# HVPulser0_1.net
KiCad netlist of a schematic drawn in EAGLE
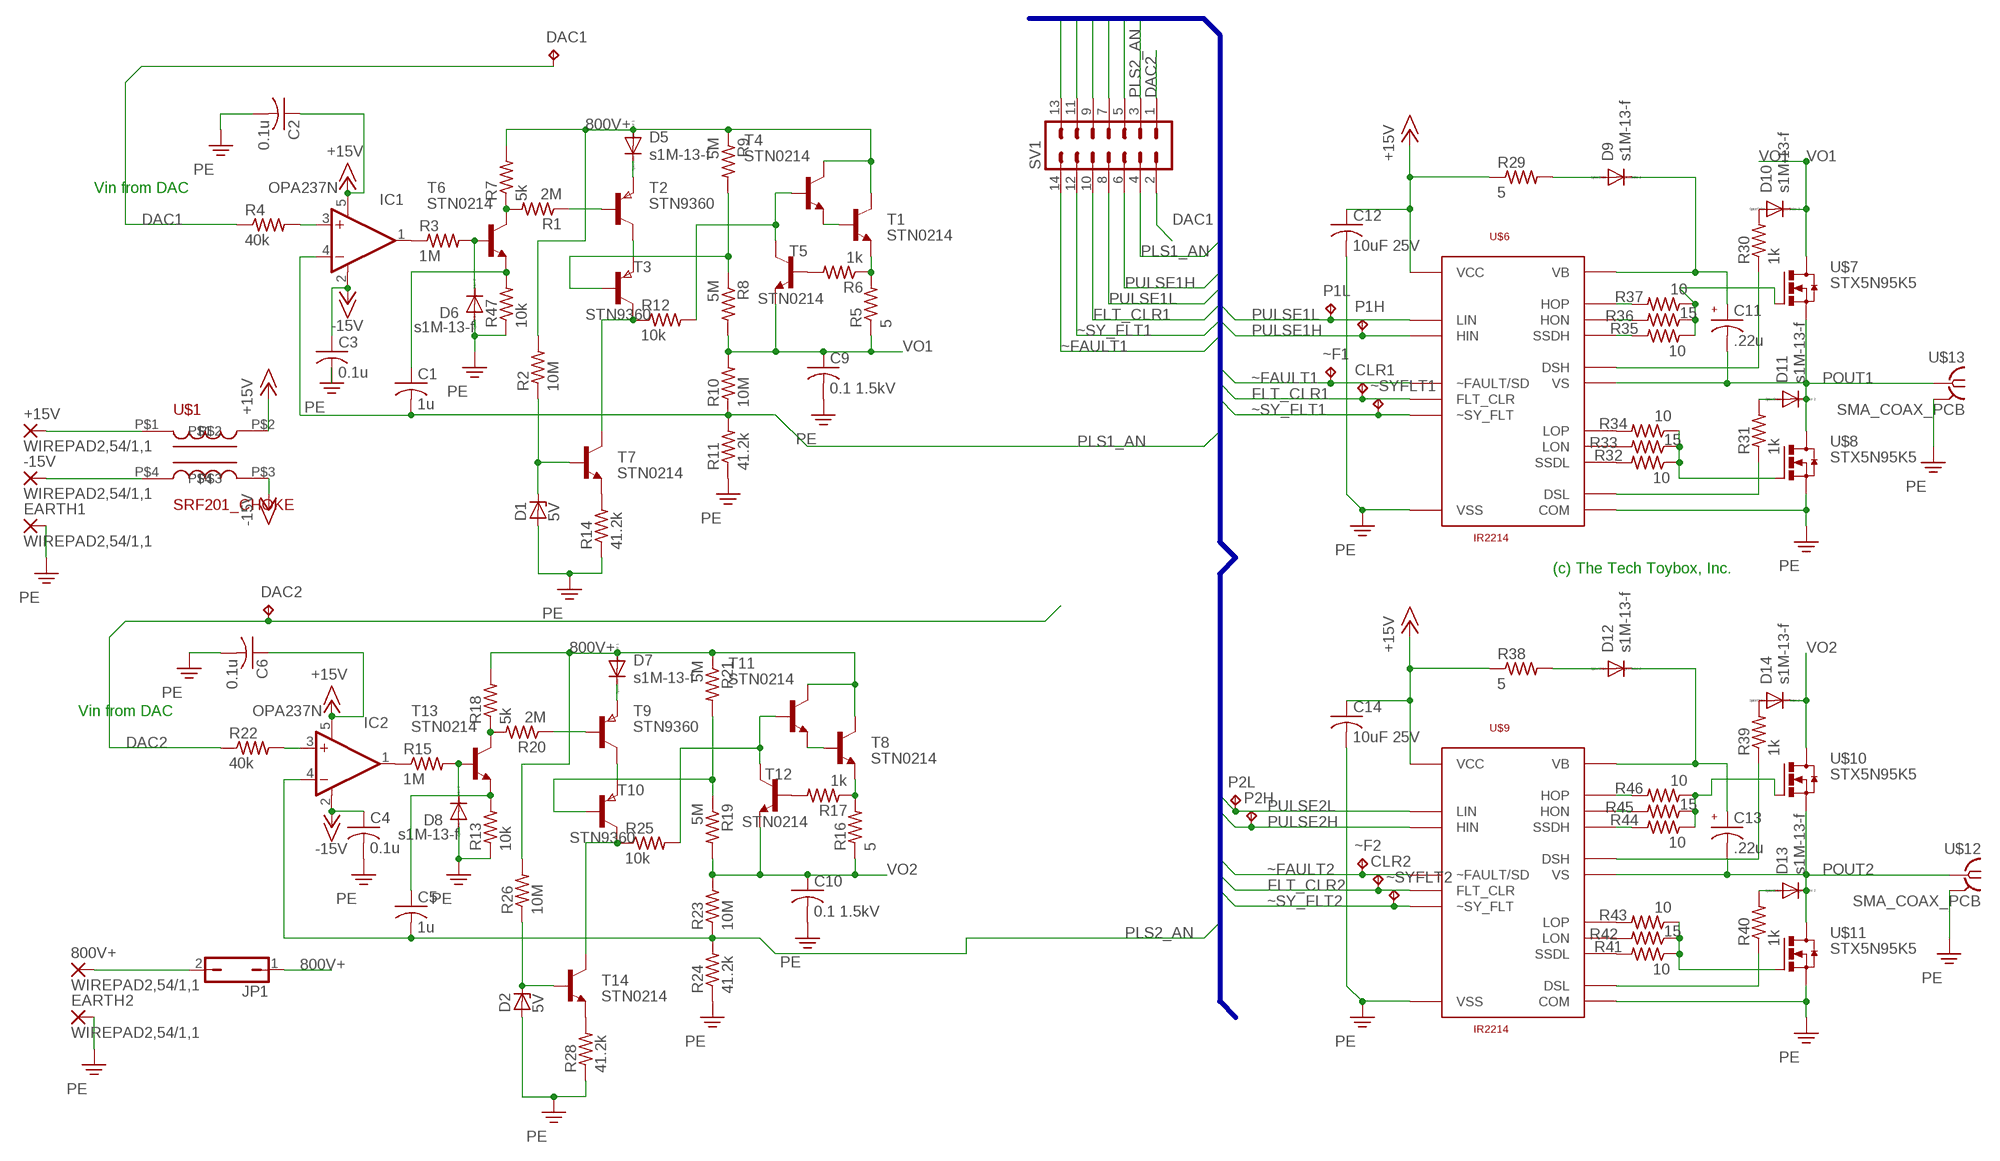
[diagram p0: schematic, sheet 1]

(export (version "E")
  (design (tool "Eeschema 10.0.6"))
  (components
    (comp (ref "+15V")
      (value "WIREPAD2,54/1,1")
      (footprint "eagle-import:2,54_1,1")
      (libsource (lib "eagle-import") (part "WIREPAD2,54/1,1"))
    )
    (comp (ref "-15V")
      (value "WIREPAD2,54/1,1")
      (footprint "eagle-import:2,54_1,1")
      (libsource (lib "eagle-import") (part "WIREPAD2,54/1,1"))
    )
    (comp (ref "800V+")
      (value "WIREPAD2,54/1,1")
      (footprint "eagle-import:2,54_1,1")
      (libsource (lib "eagle-import") (part "WIREPAD2,54/1,1"))
    )
    (comp (ref "C1")
      (value "1u")
      (footprint "eagle-import:C0805")
      (libsource (lib "eagle-import") (part "rcl_C-USC0805"))
    )
    (comp (ref "C2")
      (value "0.1u")
      (footprint "eagle-import:C0805")
      (libsource (lib "eagle-import") (part "rcl_C-USC0805"))
    )
    (comp (ref "C3")
      (value "0.1u")
      (footprint "eagle-import:C0805")
      (libsource (lib "eagle-import") (part "rcl_C-USC0805"))
    )
    (comp (ref "C4")
      (value "0.1u")
      (footprint "eagle-import:C0805")
      (libsource (lib "eagle-import") (part "rcl_C-USC0805"))
    )
    (comp (ref "C5")
      (value "1u")
      (footprint "eagle-import:C0805")
      (libsource (lib "eagle-import") (part "rcl_C-USC0805"))
    )
    (comp (ref "C6")
      (value "0.1u")
      (footprint "eagle-import:C0805")
      (libsource (lib "eagle-import") (part "rcl_C-USC0805"))
    )
    (comp (ref "C9")
      (value "0.1 1.5kV")
      (footprint "eagle-import:C2225K")
      (libsource (lib "eagle-import") (part "rcl_C-USC2225K"))
    )
    (comp (ref "C10")
      (value "0.1 1.5kV")
      (footprint "eagle-import:C2225K")
      (libsource (lib "eagle-import") (part "rcl_C-USC2225K"))
    )
    (comp (ref "C11")
      (value ".22u")
      (footprint "eagle-import:C050-035X075")
      (fields (field (name "PARTNO") "C1608X7R1H224K080AB"))
      (libsource (lib "eagle-import") (part "C-US050-035X075"))
    )
    (comp (ref "C12")
      (value "10uF 25V")
      (footprint "eagle-import:C0805")
      (libsource (lib "eagle-import") (part "rcl_C-USC0805"))
    )
    (comp (ref "C13")
      (value ".22u")
      (footprint "eagle-import:C050-035X075")
      (fields (field (name "PARTNO") "C1608X7R1H224K080AB"))
      (libsource (lib "eagle-import") (part "C-US050-035X075"))
    )
    (comp (ref "C14")
      (value "10uF 25V")
      (footprint "eagle-import:C0805")
      (libsource (lib "eagle-import") (part "rcl_C-USC0805"))
    )
    (comp (ref "CLR1")
      (value "TPTP10R")
      (footprint "eagle-import:TP10R")
      (libsource (lib "eagle-import") (part "TPTP10R"))
    )
    (comp (ref "CLR2")
      (value "TPTP10R")
      (footprint "eagle-import:TP10R")
      (libsource (lib "eagle-import") (part "TPTP10R"))
    )
    (comp (ref "D1")
      (value "5V")
      (footprint "eagle-import:DO41Z10")
      (libsource (lib "eagle-import") (part "ZENER-DIODEDO41Z10"))
    )
    (comp (ref "D2")
      (value "5V")
      (footprint "eagle-import:DO41Z10")
      (libsource (lib "eagle-import") (part "ZENER-DIODEDO41Z10"))
    )
    (comp (ref "D5")
      (value "s1M-13-f")
      (footprint "eagle-import:DO214AC")
      (libsource (lib "eagle-import") (part "DIODE-DO214AC"))
    )
    (comp (ref "D6")
      (value "s1M-13-f")
      (footprint "eagle-import:DO214AC")
      (libsource (lib "eagle-import") (part "DIODE-DO214AC"))
    )
    (comp (ref "D7")
      (value "s1M-13-f")
      (footprint "eagle-import:DO214AC")
      (libsource (lib "eagle-import") (part "DIODE-DO214AC"))
    )
    (comp (ref "D8")
      (value "s1M-13-f")
      (footprint "eagle-import:DO214AC")
      (libsource (lib "eagle-import") (part "DIODE-DO214AC"))
    )
    (comp (ref "D9")
      (value "s1M-13-f")
      (footprint "eagle-import:DO214AC")
      (libsource (lib "eagle-import") (part "DIODE-DO214AC"))
    )
    (comp (ref "D10")
      (value "s1M-13-f")
      (footprint "eagle-import:DO214AC")
      (libsource (lib "eagle-import") (part "DIODE-DO214AC"))
    )
    (comp (ref "D11")
      (value "s1M-13-f")
      (footprint "eagle-import:DO214AC")
      (libsource (lib "eagle-import") (part "DIODE-DO214AC"))
    )
    (comp (ref "D12")
      (value "s1M-13-f")
      (footprint "eagle-import:DO214AC")
      (libsource (lib "eagle-import") (part "DIODE-DO214AC"))
    )
    (comp (ref "D13")
      (value "s1M-13-f")
      (footprint "eagle-import:DO214AC")
      (libsource (lib "eagle-import") (part "DIODE-DO214AC"))
    )
    (comp (ref "D14")
      (value "s1M-13-f")
      (footprint "eagle-import:DO214AC")
      (libsource (lib "eagle-import") (part "DIODE-DO214AC"))
    )
    (comp (ref "DAC1")
      (value "TPTP10R")
      (footprint "eagle-import:TP10R")
      (libsource (lib "eagle-import") (part "TPTP10R"))
    )
    (comp (ref "DAC2")
      (value "TPTP10R")
      (footprint "eagle-import:TP10R")
      (libsource (lib "eagle-import") (part "TPTP10R"))
    )
    (comp (ref "EARTH1")
      (value "WIREPAD2,54/1,1")
      (footprint "eagle-import:2,54_1,1")
      (libsource (lib "eagle-import") (part "WIREPAD2,54/1,1"))
    )
    (comp (ref "EARTH2")
      (value "WIREPAD2,54/1,1")
      (footprint "eagle-import:2,54_1,1")
      (libsource (lib "eagle-import") (part "WIREPAD2,54/1,1"))
    )
    (comp (ref "IC1")
      (value "OPA237N")
      (footprint "eagle-import:SOT23-5")
      (fields (field (name "MF") "TEXAS INSTRUMENTS") (field (name "MPN") "OPA237NA/250"))
      (libsource (lib "eagle-import") (part "OPA237N"))
    )
    (comp (ref "IC2")
      (value "OPA237N")
      (footprint "eagle-import:SOT23-5")
      (fields (field (name "MF") "TEXAS INSTRUMENTS") (field (name "MPN") "OPA237NA/250"))
      (libsource (lib "eagle-import") (part "OPA237N"))
    )
    (comp (ref "JP1")
      (value "JP1Q")
      (footprint "eagle-import:JP1")
      (libsource (lib "eagle-import") (part "JP1Q"))
    )
    (comp (ref "P1H")
      (value "TPTP10R")
      (footprint "eagle-import:TP10R")
      (libsource (lib "eagle-import") (part "TPTP10R"))
    )
    (comp (ref "P1L")
      (value "TPTP10R")
      (footprint "eagle-import:TP10R")
      (libsource (lib "eagle-import") (part "TPTP10R"))
    )
    (comp (ref "P2H")
      (value "TPTP10R")
      (footprint "eagle-import:TP10R")
      (libsource (lib "eagle-import") (part "TPTP10R"))
    )
    (comp (ref "P2L")
      (value "TPTP10R")
      (footprint "eagle-import:TP10R")
      (libsource (lib "eagle-import") (part "TPTP10R"))
    )
    (comp (ref "R1")
      (value "2M")
      (footprint "eagle-import:P0613_15")
      (libsource (lib "eagle-import") (part "R-US_0613/15"))
    )
    (comp (ref "R2")
      (value "10M")
      (footprint "eagle-import:P0613_15")
      (libsource (lib "eagle-import") (part "R-US_0613/15"))
    )
    (comp (ref "R3")
      (value "1M")
      (footprint "eagle-import:R0603")
      (libsource (lib "eagle-import") (part "R-US_R0603"))
    )
    (comp (ref "R4")
      (value "40k")
      (footprint "eagle-import:R0603")
      (libsource (lib "eagle-import") (part "R-US_R0603"))
    )
    (comp (ref "R5")
      (value "5")
      (footprint "eagle-import:P0613_15")
      (libsource (lib "eagle-import") (part "R-US_0613/15"))
    )
    (comp (ref "R6")
      (value "1k")
      (footprint "eagle-import:P0613_15")
      (libsource (lib "eagle-import") (part "R-US_0613/15"))
    )
    (comp (ref "R7")
      (value "5k")
      (footprint "eagle-import:R0603")
      (libsource (lib "eagle-import") (part "R-US_R0603"))
    )
    (comp (ref "R8")
      (value "5M")
      (footprint "eagle-import:P0613_15")
      (libsource (lib "eagle-import") (part "R-US_0613/15"))
    )
    (comp (ref "R9")
      (value "5M")
      (footprint "eagle-import:P0613_15")
      (libsource (lib "eagle-import") (part "R-US_0613/15"))
    )
    (comp (ref "R10")
      (value "10M")
      (footprint "eagle-import:P0613_15")
      (libsource (lib "eagle-import") (part "R-US_0613/15"))
    )
    (comp (ref "R11")
      (value "41.2k")
      (footprint "eagle-import:P0613_15")
      (libsource (lib "eagle-import") (part "R-US_0613/15"))
    )
    (comp (ref "R12")
      (value "10k")
      (footprint "eagle-import:R0603")
      (libsource (lib "eagle-import") (part "R-US_R0603"))
    )
    (comp (ref "R13")
      (value "10k")
      (footprint "eagle-import:R0805")
      (libsource (lib "eagle-import") (part "R-US_R0805"))
    )
    (comp (ref "R14")
      (value "41.2k")
      (footprint "eagle-import:P0613_15")
      (libsource (lib "eagle-import") (part "R-US_0613/15"))
    )
    (comp (ref "R15")
      (value "1M")
      (footprint "eagle-import:R0603")
      (libsource (lib "eagle-import") (part "R-US_R0603"))
    )
    (comp (ref "R16")
      (value "5")
      (footprint "eagle-import:P0613_15")
      (libsource (lib "eagle-import") (part "R-US_0613/15"))
    )
    (comp (ref "R17")
      (value "1k")
      (footprint "eagle-import:P0613_15")
      (libsource (lib "eagle-import") (part "R-US_0613/15"))
    )
    (comp (ref "R18")
      (value "5k")
      (footprint "eagle-import:R0603")
      (libsource (lib "eagle-import") (part "R-US_R0603"))
    )
    (comp (ref "R19")
      (value "5M")
      (footprint "eagle-import:P0613_15")
      (libsource (lib "eagle-import") (part "R-US_0613/15"))
    )
    (comp (ref "R20")
      (value "2M")
      (footprint "eagle-import:P0613_15")
      (libsource (lib "eagle-import") (part "R-US_0613/15"))
    )
    (comp (ref "R21")
      (value "5M")
      (footprint "eagle-import:P0613_15")
      (libsource (lib "eagle-import") (part "R-US_0613/15"))
    )
    (comp (ref "R22")
      (value "40k")
      (footprint "eagle-import:R0603")
      (libsource (lib "eagle-import") (part "R-US_R0603"))
    )
    (comp (ref "R23")
      (value "10M")
      (footprint "eagle-import:P0613_15")
      (libsource (lib "eagle-import") (part "R-US_0613/15"))
    )
    (comp (ref "R24")
      (value "41.2k")
      (footprint "eagle-import:P0613_15")
      (libsource (lib "eagle-import") (part "R-US_0613/15"))
    )
    (comp (ref "R25")
      (value "10k")
      (footprint "eagle-import:R0603")
      (libsource (lib "eagle-import") (part "R-US_R0603"))
    )
    (comp (ref "R26")
      (value "10M")
      (footprint "eagle-import:P0613_15")
      (libsource (lib "eagle-import") (part "R-US_0613/15"))
    )
    (comp (ref "R28")
      (value "41.2k")
      (footprint "eagle-import:P0613_15")
      (libsource (lib "eagle-import") (part "R-US_0613/15"))
    )
    (comp (ref "R29")
      (value "5")
      (footprint "eagle-import:0207_10")
      (libsource (lib "eagle-import") (part "R-US_0207/10"))
    )
    (comp (ref "R30")
      (value "1k")
      (footprint "eagle-import:R0603")
      (libsource (lib "eagle-import") (part "R-US_R0603"))
    )
    (comp (ref "R31")
      (value "1k")
      (footprint "eagle-import:R0603")
      (libsource (lib "eagle-import") (part "R-US_R0603"))
    )
    (comp (ref "R32")
      (value "10")
      (footprint "eagle-import:R0805")
      (libsource (lib "eagle-import") (part "R-US_R0805"))
    )
    (comp (ref "R33")
      (value "15")
      (footprint "eagle-import:R0805")
      (libsource (lib "eagle-import") (part "R-US_R0805"))
    )
    (comp (ref "R34")
      (value "10")
      (footprint "eagle-import:R0805")
      (libsource (lib "eagle-import") (part "R-US_R0805"))
    )
    (comp (ref "R35")
      (value "10")
      (footprint "eagle-import:R0805")
      (libsource (lib "eagle-import") (part "R-US_R0805"))
    )
    (comp (ref "R36")
      (value "15")
      (footprint "eagle-import:R0805")
      (libsource (lib "eagle-import") (part "R-US_R0805"))
    )
    (comp (ref "R37")
      (value "10")
      (footprint "eagle-import:R0805")
      (libsource (lib "eagle-import") (part "R-US_R0805"))
    )
    (comp (ref "R38")
      (value "5")
      (footprint "eagle-import:0207_10")
      (libsource (lib "eagle-import") (part "R-US_0207/10"))
    )
    (comp (ref "R39")
      (value "1k")
      (footprint "eagle-import:R0603")
      (libsource (lib "eagle-import") (part "R-US_R0603"))
    )
    (comp (ref "R40")
      (value "1k")
      (footprint "eagle-import:R0603")
      (libsource (lib "eagle-import") (part "R-US_R0603"))
    )
    (comp (ref "R41")
      (value "10")
      (footprint "eagle-import:R0805")
      (libsource (lib "eagle-import") (part "R-US_R0805"))
    )
    (comp (ref "R42")
      (value "15")
      (footprint "eagle-import:R0805")
      (libsource (lib "eagle-import") (part "R-US_R0805"))
    )
    (comp (ref "R43")
      (value "10")
      (footprint "eagle-import:R0805")
      (libsource (lib "eagle-import") (part "R-US_R0805"))
    )
    (comp (ref "R44")
      (value "10")
      (footprint "eagle-import:R0805")
      (libsource (lib "eagle-import") (part "R-US_R0805"))
    )
    (comp (ref "R45")
      (value "15")
      (footprint "eagle-import:R0805")
      (libsource (lib "eagle-import") (part "R-US_R0805"))
    )
    (comp (ref "R46")
      (value "10")
      (footprint "eagle-import:R0805")
      (libsource (lib "eagle-import") (part "R-US_R0805"))
    )
    (comp (ref "R47")
      (value "10k")
      (footprint "eagle-import:R0805")
      (libsource (lib "eagle-import") (part "R-US_R0805"))
    )
    (comp (ref "SV1")
      (value "MA07-2")
      (footprint "eagle-import:MA07-2")
      (libsource (lib "eagle-import") (part "MA07-2"))
    )
    (comp (ref "T1")
      (value "STN0214")
      (footprint "eagle-import:SOT223")
      (libsource (lib "eagle-import") (part "-NPN-SOT223"))
    )
    (comp (ref "T2")
      (value "STN9360")
      (footprint "eagle-import:SOT223")
      (fields (field (name "MPN") "DJT4030P-13"))
      (libsource (lib "eagle-import") (part "PNPSOT223"))
    )
    (comp (ref "T3")
      (value "STN9360")
      (footprint "eagle-import:SOT223")
      (fields (field (name "MPN") "DJT4030P-13"))
      (libsource (lib "eagle-import") (part "PNPSOT223"))
    )
    (comp (ref "T4")
      (value "STN0214")
      (footprint "eagle-import:SOT223")
      (libsource (lib "eagle-import") (part "-NPN-SOT223"))
    )
    (comp (ref "T5")
      (value "STN0214")
      (footprint "eagle-import:SOT223")
      (libsource (lib "eagle-import") (part "-NPN-SOT223"))
    )
    (comp (ref "T6")
      (value "STN0214")
      (footprint "eagle-import:SOT223")
      (libsource (lib "eagle-import") (part "-NPN-SOT223"))
    )
    (comp (ref "T7")
      (value "STN0214")
      (footprint "eagle-import:SOT223")
      (libsource (lib "eagle-import") (part "-NPN-SOT223"))
    )
    (comp (ref "T8")
      (value "STN0214")
      (footprint "eagle-import:SOT223")
      (libsource (lib "eagle-import") (part "-NPN-SOT223"))
    )
    (comp (ref "T9")
      (value "STN9360")
      (footprint "eagle-import:SOT223")
      (fields (field (name "MPN") "DJT4030P-13"))
      (libsource (lib "eagle-import") (part "PNPSOT223"))
    )
    (comp (ref "T10")
      (value "STN9360")
      (footprint "eagle-import:SOT223")
      (fields (field (name "MPN") "DJT4030P-13"))
      (libsource (lib "eagle-import") (part "PNPSOT223"))
    )
    (comp (ref "T11")
      (value "STN0214")
      (footprint "eagle-import:SOT223")
      (libsource (lib "eagle-import") (part "-NPN-SOT223"))
    )
    (comp (ref "T12")
      (value "STN0214")
      (footprint "eagle-import:SOT223")
      (libsource (lib "eagle-import") (part "-NPN-SOT223"))
    )
    (comp (ref "T13")
      (value "STN0214")
      (footprint "eagle-import:SOT223")
      (libsource (lib "eagle-import") (part "-NPN-SOT223"))
    )
    (comp (ref "T14")
      (value "STN0214")
      (footprint "eagle-import:SOT223")
      (libsource (lib "eagle-import") (part "-NPN-SOT223"))
    )
    (comp (ref "U$1")
      (value "SRF201_CHOKE")
      (footprint "eagle-import:CHOKE_BOURNES_SRF2012")
      (libsource (lib "eagle-import") (part "SRF201_CHOKE"))
    )
    (comp (ref "U$6")
      (value "IR2214")
      (footprint "eagle-import:SSOP24-IR-0.65")
      (libsource (lib "eagle-import") (part "IR2214"))
    )
    (comp (ref "U$7")
      (value "STX5N95K5")
      (footprint "eagle-import:TO220AV")
      (libsource (lib "eagle-import") (part "STX5N95K5"))
    )
    (comp (ref "U$8")
      (value "STX5N95K5")
      (footprint "eagle-import:TO220AV")
      (libsource (lib "eagle-import") (part "STX5N95K5"))
    )
    (comp (ref "U$9")
      (value "IR2214")
      (footprint "eagle-import:SSOP24-IR-0.65")
      (libsource (lib "eagle-import") (part "IR2214"))
    )
    (comp (ref "U$10")
      (value "STX5N95K5")
      (footprint "eagle-import:TO220AV")
      (libsource (lib "eagle-import") (part "STX5N95K5"))
    )
    (comp (ref "U$11")
      (value "STX5N95K5")
      (footprint "eagle-import:TO220AV")
      (libsource (lib "eagle-import") (part "STX5N95K5"))
    )
    (comp (ref "U$12")
      (value "SMA_COAX_PCB")
      (footprint "eagle-import:SMA-COAX-V-TECONNECT")
      (libsource (lib "eagle-import") (part "SMA_COAX_PCB"))
    )
    (comp (ref "U$13")
      (value "SMA_COAX_PCB")
      (footprint "eagle-import:SMA-COAX-V-TECONNECT")
      (libsource (lib "eagle-import") (part "SMA_COAX_PCB"))
    )
    (comp (ref "~F1")
      (value "TPTP10R")
      (footprint "eagle-import:TP10R")
      (libsource (lib "eagle-import") (part "TPTP10R"))
    )
    (comp (ref "~F2")
      (value "TPTP10R")
      (footprint "eagle-import:TP10R")
      (libsource (lib "eagle-import") (part "TPTP10R"))
    )
    (comp (ref "~SYFLT1")
      (value "TPTP10R")
      (footprint "eagle-import:TP10R")
      (libsource (lib "eagle-import") (part "TPTP10R"))
    )
    (comp (ref "~SYFLT2")
      (value "TPTP10R")
      (footprint "eagle-import:TP10R")
      (libsource (lib "eagle-import") (part "TPTP10R"))
    )
  )
  (nets
    (net (code "1") (name "+15V") (class "Default")
      (node (ref "C12") (pin "1") (pinfunction "1_1") (pintype "passive"))
      (node (ref "C14") (pin "1") (pinfunction "1_1") (pintype "passive"))
      (node (ref "C2") (pin "1") (pinfunction "1_1") (pintype "passive"))
      (node (ref "C6") (pin "1") (pinfunction "1_1") (pintype "passive"))
      (node (ref "IC1") (pin "5") (pinfunction "V+_5") (pintype "power_in"))
      (node (ref "IC2") (pin "5") (pinfunction "V+_5") (pintype "power_in"))
      (node (ref "R29") (pin "1") (pinfunction "1_1") (pintype "passive"))
      (node (ref "R38") (pin "1") (pinfunction "1_1") (pintype "passive"))
      (node (ref "U$1") (pin "P$2") (pinfunction "P$2_P$2") (pintype "bidirectional"))
      (node (ref "U$6") (pin "P$11") (pinfunction "VCC_P$11") (pintype "bidirectional"))
      (node (ref "U$9") (pin "P$11") (pinfunction "VCC_P$11") (pintype "bidirectional"))
    )
    (net (code "2") (name "-15V") (class "Default")
      (node (ref "C3") (pin "1") (pinfunction "1_1") (pintype "passive"))
      (node (ref "C4") (pin "1") (pinfunction "1_1") (pintype "passive"))
      (node (ref "IC1") (pin "2") (pinfunction "V-_2") (pintype "power_in"))
      (node (ref "IC2") (pin "2") (pinfunction "V-_2") (pintype "power_in"))
      (node (ref "U$1") (pin "P$3") (pinfunction "P$3_P$3") (pintype "bidirectional"))
    )
    (net (code "3") (name "/800V+") (class "Default")
      (node (ref "D5") (pin "A") (pinfunction "A_A") (pintype "passive"))
      (node (ref "D7") (pin "A") (pinfunction "A_A") (pintype "passive"))
      (node (ref "JP1") (pin "1") (pinfunction "1_1") (pintype "passive"))
      (node (ref "R18") (pin "2") (pinfunction "2_2") (pintype "passive"))
      (node (ref "R2") (pin "2") (pinfunction "2_2") (pintype "passive"))
      (node (ref "R21") (pin "1") (pinfunction "1_1") (pintype "passive"))
      (node (ref "R26") (pin "2") (pinfunction "2_2") (pintype "passive"))
      (node (ref "R7") (pin "2") (pinfunction "2_2") (pintype "passive"))
      (node (ref "R9") (pin "1") (pinfunction "1_1") (pintype "passive"))
      (node (ref "T1") (pin "4") (pinfunction "C_4") (pintype "passive"))
      (node (ref "T11") (pin "4") (pinfunction "C_4") (pintype "passive"))
      (node (ref "T4") (pin "4") (pinfunction "C_4") (pintype "passive"))
      (node (ref "T8") (pin "4") (pinfunction "C_4") (pintype "passive"))
    )
    (net (code "4") (name "/DAC1") (class "Default")
      (node (ref "DAC1") (pin "TP") (pinfunction "TP_TP") (pintype "input"))
      (node (ref "R4") (pin "1") (pinfunction "1_1") (pintype "passive"))
      (node (ref "SV1") (pin "2") (pinfunction "2_2") (pintype "passive"))
    )
    (net (code "5") (name "/DAC2") (class "Default")
      (node (ref "DAC2") (pin "TP") (pinfunction "TP_TP") (pintype "input"))
      (node (ref "R22") (pin "1") (pinfunction "1_1") (pintype "passive"))
      (node (ref "SV1") (pin "1") (pinfunction "1_1") (pintype "passive"))
    )
    (net (code "6") (name "/FLT_CLR1") (class "Default")
      (node (ref "CLR1") (pin "TP") (pinfunction "TP_TP") (pintype "input"))
      (node (ref "SV1") (pin "10") (pinfunction "10_10") (pintype "passive"))
      (node (ref "U$6") (pin "P$3") (pinfunction "FLT_CLR_P$3") (pintype "bidirectional"))
    )
    (net (code "7") (name "/FLT_CLR2") (class "Default")
      (node (ref "CLR2") (pin "TP") (pinfunction "TP_TP") (pintype "input"))
      (node (ref "SV1") (pin "9") (pinfunction "9_9") (pintype "passive"))
      (node (ref "U$9") (pin "P$3") (pinfunction "FLT_CLR_P$3") (pintype "bidirectional"))
    )
    (net (code "8") (name "/PLS1_AN") (class "Default")
      (node (ref "C1") (pin "2") (pinfunction "2_2") (pintype "passive"))
      (node (ref "IC1") (pin "4") (pinfunction "-IN_4") (pintype "input"))
      (node (ref "R10") (pin "1") (pinfunction "1_1") (pintype "passive"))
      (node (ref "R11") (pin "2") (pinfunction "2_2") (pintype "passive"))
      (node (ref "SV1") (pin "4") (pinfunction "4_4") (pintype "passive"))
    )
    (net (code "9") (name "/PLS2_AN") (class "Default")
      (node (ref "C5") (pin "2") (pinfunction "2_2") (pintype "passive"))
      (node (ref "IC2") (pin "4") (pinfunction "-IN_4") (pintype "input"))
      (node (ref "R23") (pin "1") (pinfunction "1_1") (pintype "passive"))
      (node (ref "R24") (pin "2") (pinfunction "2_2") (pintype "passive"))
      (node (ref "SV1") (pin "3") (pinfunction "3_3") (pintype "passive"))
    )
    (net (code "10") (name "/POUT1") (class "Default")
      (node (ref "C11") (pin "2") (pinfunction "2_2") (pintype "passive"))
      (node (ref "D11") (pin "C") (pinfunction "C_C") (pintype "passive"))
      (node (ref "U$13") (pin "1") (pinfunction "1_1") (pintype "passive"))
      (node (ref "U$6") (pin "P$19") (pinfunction "VS_P$19") (pintype "bidirectional"))
      (node (ref "U$7") (pin "3") (pinfunction "S_3") (pintype "passive"))
      (node (ref "U$8") (pin "2") (pinfunction "D_2") (pintype "passive"))
    )
    (net (code "11") (name "/POUT2") (class "Default")
      (node (ref "C13") (pin "2") (pinfunction "2_2") (pintype "passive"))
      (node (ref "D13") (pin "C") (pinfunction "C_C") (pintype "passive"))
      (node (ref "U$10") (pin "3") (pinfunction "S_3") (pintype "passive"))
      (node (ref "U$11") (pin "2") (pinfunction "D_2") (pintype "passive"))
      (node (ref "U$12") (pin "1") (pinfunction "1_1") (pintype "passive"))
      (node (ref "U$9") (pin "P$19") (pinfunction "VS_P$19") (pintype "bidirectional"))
    )
    (net (code "12") (name "/PULSE1H") (class "Default")
      (node (ref "P1H") (pin "TP") (pinfunction "TP_TP") (pintype "input"))
      (node (ref "SV1") (pin "6") (pinfunction "6_6") (pintype "passive"))
      (node (ref "U$6") (pin "P$1") (pinfunction "HIN_P$1") (pintype "input"))
    )
    (net (code "13") (name "/PULSE1L") (class "Default")
      (node (ref "P1L") (pin "TP") (pinfunction "TP_TP") (pintype "input"))
      (node (ref "SV1") (pin "8") (pinfunction "8_8") (pintype "passive"))
      (node (ref "U$6") (pin "P$2") (pinfunction "LIN_P$2") (pintype "input"))
    )
    (net (code "14") (name "/PULSE2H") (class "Default")
      (node (ref "P2H") (pin "TP") (pinfunction "TP_TP") (pintype "input"))
      (node (ref "SV1") (pin "13") (pinfunction "13_13") (pintype "passive"))
      (node (ref "U$9") (pin "P$1") (pinfunction "HIN_P$1") (pintype "input"))
    )
    (net (code "15") (name "/PULSE2L") (class "Default")
      (node (ref "P2L") (pin "TP") (pinfunction "TP_TP") (pintype "input"))
      (node (ref "SV1") (pin "11") (pinfunction "11_11") (pintype "passive"))
      (node (ref "U$9") (pin "P$2") (pinfunction "LIN_P$2") (pintype "input"))
    )
    (net (code "16") (name "/VO1") (class "Default")
      (node (ref "C9") (pin "1") (pinfunction "1_1") (pintype "passive"))
      (node (ref "D10") (pin "C") (pinfunction "C_C") (pintype "passive"))
      (node (ref "R10") (pin "2") (pinfunction "2_2") (pintype "passive"))
      (node (ref "R5") (pin "1") (pinfunction "1_1") (pintype "passive"))
      (node (ref "R8") (pin "2") (pinfunction "2_2") (pintype "passive"))
      (node (ref "T5") (pin "3") (pinfunction "E_3") (pintype "passive"))
      (node (ref "U$7") (pin "2") (pinfunction "D_2") (pintype "passive"))
    )
    (net (code "17") (name "/VO2") (class "Default")
      (node (ref "C10") (pin "1") (pinfunction "1_1") (pintype "passive"))
      (node (ref "D14") (pin "C") (pinfunction "C_C") (pintype "passive"))
      (node (ref "R16") (pin "1") (pinfunction "1_1") (pintype "passive"))
      (node (ref "R19") (pin "2") (pinfunction "2_2") (pintype "passive"))
      (node (ref "R23") (pin "2") (pinfunction "2_2") (pintype "passive"))
      (node (ref "T12") (pin "3") (pinfunction "E_3") (pintype "passive"))
      (node (ref "U$10") (pin "2") (pinfunction "D_2") (pintype "passive"))
    )
    (net (code "18") (name "/~{FAULT1}") (class "Default")
      (node (ref "SV1") (pin "14") (pinfunction "14_14") (pintype "passive"))
      (node (ref "U$6") (pin "P$5") (pinfunction "~{FAULT/SD}_P$5") (pintype "bidirectional"))
      (node (ref "~F1") (pin "TP") (pinfunction "TP_TP") (pintype "input"))
    )
    (net (code "19") (name "/~{FAULT2}") (class "Default")
      (node (ref "SV1") (pin "5") (pinfunction "5_5") (pintype "passive"))
      (node (ref "U$9") (pin "P$5") (pinfunction "~{FAULT/SD}_P$5") (pintype "bidirectional"))
      (node (ref "~F2") (pin "TP") (pinfunction "TP_TP") (pintype "input"))
    )
    (net (code "20") (name "/~{SY_FLT1}") (class "Default")
      (node (ref "SV1") (pin "12") (pinfunction "12_12") (pintype "passive"))
      (node (ref "U$6") (pin "P$4") (pinfunction "~{SY_FLT}_P$4") (pintype "bidirectional"))
      (node (ref "~SYFLT1") (pin "TP") (pinfunction "TP_TP") (pintype "input"))
    )
    (net (code "21") (name "/~{SY_FLT2}") (class "Default")
      (node (ref "SV1") (pin "7") (pinfunction "7_7") (pintype "passive"))
      (node (ref "U$9") (pin "P$4") (pinfunction "~{SY_FLT}_P$4") (pintype "bidirectional"))
      (node (ref "~SYFLT2") (pin "TP") (pinfunction "TP_TP") (pintype "input"))
    )
    (net (code "22") (name "Net-(+15V-P)") (class "Default")
      (node (ref "+15V") (pin "1") (pinfunction "P_1") (pintype "passive"))
      (node (ref "U$1") (pin "P$1") (pinfunction "P$1_P$1") (pintype "bidirectional"))
    )
    (net (code "23") (name "Net-(-15V-P)") (class "Default")
      (node (ref "-15V") (pin "1") (pinfunction "P_1") (pintype "passive"))
      (node (ref "U$1") (pin "P$4") (pinfunction "P$4_P$4") (pintype "bidirectional"))
    )
    (net (code "24") (name "Net-(800V+-P)") (class "Default")
      (node (ref "800V+") (pin "1") (pinfunction "P_1") (pintype "passive"))
      (node (ref "JP1") (pin "2") (pinfunction "2_2") (pintype "passive"))
    )
    (net (code "25") (name "Net-(D9-PadA)") (class "Default")
      (node (ref "D9") (pin "A") (pinfunction "A_A") (pintype "passive"))
      (node (ref "R29") (pin "2") (pinfunction "2_2") (pintype "passive"))
    )
    (net (code "26") (name "Net-(D10-PadA)") (class "Default")
      (node (ref "D10") (pin "A") (pinfunction "A_A") (pintype "passive"))
      (node (ref "R30") (pin "2") (pinfunction "2_2") (pintype "passive"))
    )
    (net (code "27") (name "Net-(D11-PadA)") (class "Default")
      (node (ref "D11") (pin "A") (pinfunction "A_A") (pintype "passive"))
      (node (ref "R31") (pin "2") (pinfunction "2_2") (pintype "passive"))
    )
    (net (code "28") (name "Net-(D12-PadA)") (class "Default")
      (node (ref "D12") (pin "A") (pinfunction "A_A") (pintype "passive"))
      (node (ref "R38") (pin "2") (pinfunction "2_2") (pintype "passive"))
    )
    (net (code "29") (name "Net-(D13-PadA)") (class "Default")
      (node (ref "D13") (pin "A") (pinfunction "A_A") (pintype "passive"))
      (node (ref "R40") (pin "2") (pinfunction "2_2") (pintype "passive"))
    )
    (net (code "30") (name "Net-(D14-PadA)") (class "Default")
      (node (ref "D14") (pin "A") (pinfunction "A_A") (pintype "passive"))
      (node (ref "R39") (pin "2") (pinfunction "2_2") (pintype "passive"))
    )
    (net (code "31") (name "Net-(IC1-+IN)") (class "Default")
      (node (ref "IC1") (pin "3") (pinfunction "+IN_3") (pintype "input"))
      (node (ref "R4") (pin "2") (pinfunction "2_2") (pintype "passive"))
    )
    (net (code "32") (name "Net-(IC1-OUT)") (class "Default")
      (node (ref "IC1") (pin "1") (pinfunction "OUT_1") (pintype "output"))
      (node (ref "R3") (pin "1") (pinfunction "1_1") (pintype "passive"))
    )
    (net (code "33") (name "Net-(IC2-+IN)") (class "Default")
      (node (ref "IC2") (pin "3") (pinfunction "+IN_3") (pintype "input"))
      (node (ref "R22") (pin "2") (pinfunction "2_2") (pintype "passive"))
    )
    (net (code "34") (name "Net-(IC2-OUT)") (class "Default")
      (node (ref "IC2") (pin "1") (pinfunction "OUT_1") (pintype "output"))
      (node (ref "R15") (pin "1") (pinfunction "1_1") (pintype "passive"))
    )
    (net (code "35") (name "Net-(T1-B)") (class "Default")
      (node (ref "T1") (pin "1") (pinfunction "B_1") (pintype "passive"))
      (node (ref "T4") (pin "3") (pinfunction "E_3") (pintype "passive"))
    )
    (net (code "36") (name "Net-(T1-E)") (class "Default")
      (node (ref "R5") (pin "2") (pinfunction "2_2") (pintype "passive"))
      (node (ref "R6") (pin "1") (pinfunction "1_1") (pintype "passive"))
      (node (ref "T1") (pin "3") (pinfunction "E_3") (pintype "passive"))
    )
    (net (code "37") (name "Net-(T2-B)") (class "Default")
      (node (ref "R1") (pin "1") (pinfunction "1_1") (pintype "passive"))
      (node (ref "T2") (pin "1") (pinfunction "B_1") (pintype "passive"))
    )
    (net (code "38") (name "Net-(T2-E)") (class "Default")
      (node (ref "D5") (pin "C") (pinfunction "C_C") (pintype "passive"))
      (node (ref "T2") (pin "3") (pinfunction "E_3") (pintype "passive"))
    )
    (net (code "39") (name "Net-(T3-B)") (class "Default")
      (node (ref "R8") (pin "1") (pinfunction "1_1") (pintype "passive"))
      (node (ref "R9") (pin "2") (pinfunction "2_2") (pintype "passive"))
      (node (ref "T3") (pin "1") (pinfunction "B_1") (pintype "passive"))
    )
    (net (code "40") (name "Net-(T3-E)") (class "Default")
      (node (ref "T2") (pin "2") (pinfunction "C_2") (pintype "passive"))
      (node (ref "T2") (pin "4") (pinfunction "C_4") (pintype "passive"))
      (node (ref "T3") (pin "3") (pinfunction "E_3") (pintype "passive"))
    )
    (net (code "41") (name "Net-(T4-B)") (class "Default")
      (node (ref "R12") (pin "2") (pinfunction "2_2") (pintype "passive"))
      (node (ref "T4") (pin "1") (pinfunction "B_1") (pintype "passive"))
      (node (ref "T5") (pin "4") (pinfunction "C_4") (pintype "passive"))
    )
    (net (code "42") (name "Net-(T5-B)") (class "Default")
      (node (ref "R6") (pin "2") (pinfunction "2_2") (pintype "passive"))
      (node (ref "T5") (pin "1") (pinfunction "B_1") (pintype "passive"))
    )
    (net (code "43") (name "Net-(T6-B)") (class "Default")
      (node (ref "D6") (pin "C") (pinfunction "C_C") (pintype "passive"))
      (node (ref "R3") (pin "2") (pinfunction "2_2") (pintype "passive"))
      (node (ref "T6") (pin "1") (pinfunction "B_1") (pintype "passive"))
    )
    (net (code "44") (name "Net-(T6-C)") (class "Default")
      (node (ref "R1") (pin "2") (pinfunction "2_2") (pintype "passive"))
      (node (ref "R7") (pin "1") (pinfunction "1_1") (pintype "passive"))
      (node (ref "T6") (pin "4") (pinfunction "C_4") (pintype "passive"))
    )
    (net (code "45") (name "Net-(T6-E)") (class "Default")
      (node (ref "C1") (pin "1") (pinfunction "1_1") (pintype "passive"))
      (node (ref "R47") (pin "2") (pinfunction "2_2") (pintype "passive"))
      (node (ref "T6") (pin "3") (pinfunction "E_3") (pintype "passive"))
    )
    (net (code "46") (name "Net-(T7-B)") (class "Default")
      (node (ref "D1") (pin "C") (pinfunction "C_C") (pintype "passive"))
      (node (ref "R2") (pin "1") (pinfunction "1_1") (pintype "passive"))
      (node (ref "T7") (pin "1") (pinfunction "B_1") (pintype "passive"))
    )
    (net (code "47") (name "Net-(T7-C)") (class "Default")
      (node (ref "R12") (pin "1") (pinfunction "1_1") (pintype "passive"))
      (node (ref "T3") (pin "2") (pinfunction "C_2") (pintype "passive"))
      (node (ref "T3") (pin "4") (pinfunction "C_4") (pintype "passive"))
      (node (ref "T7") (pin "4") (pinfunction "C_4") (pintype "passive"))
    )
    (net (code "48") (name "Net-(T7-E)") (class "Default")
      (node (ref "R14") (pin "2") (pinfunction "2_2") (pintype "passive"))
      (node (ref "T7") (pin "3") (pinfunction "E_3") (pintype "passive"))
    )
    (net (code "49") (name "Net-(T8-E)") (class "Default")
      (node (ref "R16") (pin "2") (pinfunction "2_2") (pintype "passive"))
      (node (ref "R17") (pin "1") (pinfunction "1_1") (pintype "passive"))
      (node (ref "T8") (pin "3") (pinfunction "E_3") (pintype "passive"))
    )
    (net (code "50") (name "Net-(T9-B)") (class "Default")
      (node (ref "R20") (pin "1") (pinfunction "1_1") (pintype "passive"))
      (node (ref "T9") (pin "1") (pinfunction "B_1") (pintype "passive"))
    )
    (net (code "51") (name "Net-(T9-E)") (class "Default")
      (node (ref "D7") (pin "C") (pinfunction "C_C") (pintype "passive"))
      (node (ref "T9") (pin "3") (pinfunction "E_3") (pintype "passive"))
    )
    (net (code "52") (name "Net-(T10-B)") (class "Default")
      (node (ref "R19") (pin "1") (pinfunction "1_1") (pintype "passive"))
      (node (ref "R21") (pin "2") (pinfunction "2_2") (pintype "passive"))
      (node (ref "T10") (pin "1") (pinfunction "B_1") (pintype "passive"))
    )
    (net (code "53") (name "Net-(T10-E)") (class "Default")
      (node (ref "T10") (pin "3") (pinfunction "E_3") (pintype "passive"))
      (node (ref "T9") (pin "2") (pinfunction "C_2") (pintype "passive"))
      (node (ref "T9") (pin "4") (pinfunction "C_4") (pintype "passive"))
    )
    (net (code "54") (name "Net-(T11-B)") (class "Default")
      (node (ref "R25") (pin "2") (pinfunction "2_2") (pintype "passive"))
      (node (ref "T11") (pin "1") (pinfunction "B_1") (pintype "passive"))
      (node (ref "T12") (pin "4") (pinfunction "C_4") (pintype "passive"))
    )
    (net (code "55") (name "Net-(T11-E)") (class "Default")
      (node (ref "T11") (pin "3") (pinfunction "E_3") (pintype "passive"))
      (node (ref "T8") (pin "1") (pinfunction "B_1") (pintype "passive"))
    )
    (net (code "56") (name "Net-(T12-B)") (class "Default")
      (node (ref "R17") (pin "2") (pinfunction "2_2") (pintype "passive"))
      (node (ref "T12") (pin "1") (pinfunction "B_1") (pintype "passive"))
    )
    (net (code "57") (name "Net-(T13-B)") (class "Default")
      (node (ref "D8") (pin "C") (pinfunction "C_C") (pintype "passive"))
      (node (ref "R15") (pin "2") (pinfunction "2_2") (pintype "passive"))
      (node (ref "T13") (pin "1") (pinfunction "B_1") (pintype "passive"))
    )
    (net (code "58") (name "Net-(T13-C)") (class "Default")
      (node (ref "R18") (pin "1") (pinfunction "1_1") (pintype "passive"))
      (node (ref "R20") (pin "2") (pinfunction "2_2") (pintype "passive"))
      (node (ref "T13") (pin "4") (pinfunction "C_4") (pintype "passive"))
    )
    (net (code "59") (name "Net-(T13-E)") (class "Default")
      (node (ref "C5") (pin "1") (pinfunction "1_1") (pintype "passive"))
      (node (ref "R13") (pin "2") (pinfunction "2_2") (pintype "passive"))
      (node (ref "T13") (pin "3") (pinfunction "E_3") (pintype "passive"))
    )
    (net (code "60") (name "Net-(T14-B)") (class "Default")
      (node (ref "D2") (pin "C") (pinfunction "C_C") (pintype "passive"))
      (node (ref "R26") (pin "1") (pinfunction "1_1") (pintype "passive"))
      (node (ref "T14") (pin "1") (pinfunction "B_1") (pintype "passive"))
    )
    (net (code "61") (name "Net-(T14-C)") (class "Default")
      (node (ref "R25") (pin "1") (pinfunction "1_1") (pintype "passive"))
      (node (ref "T10") (pin "2") (pinfunction "C_2") (pintype "passive"))
      (node (ref "T10") (pin "4") (pinfunction "C_4") (pintype "passive"))
      (node (ref "T14") (pin "4") (pinfunction "C_4") (pintype "passive"))
    )
    (net (code "62") (name "Net-(T14-E)") (class "Default")
      (node (ref "R28") (pin "2") (pinfunction "2_2") (pintype "passive"))
      (node (ref "T14") (pin "3") (pinfunction "E_3") (pintype "passive"))
    )
    (net (code "63") (name "Net-(U$6-DSH)") (class "Default")
      (node (ref "R30") (pin "1") (pinfunction "1_1") (pintype "passive"))
      (node (ref "U$6") (pin "P$24") (pinfunction "DSH_P$24") (pintype "bidirectional"))
    )
    (net (code "64") (name "Net-(U$6-DSL)") (class "Default")
      (node (ref "R31") (pin "1") (pinfunction "1_1") (pintype "passive"))
      (node (ref "U$6") (pin "P$12") (pinfunction "DSL_P$12") (pintype "bidirectional"))
    )
    (net (code "65") (name "Net-(U$6-HON)") (class "Default")
      (node (ref "R36") (pin "2") (pinfunction "2_2") (pintype "passive"))
      (node (ref "U$6") (pin "P$20") (pinfunction "HON_P$20") (pintype "bidirectional"))
    )
    (net (code "66") (name "Net-(U$6-HOP)") (class "Default")
      (node (ref "R37") (pin "2") (pinfunction "2_2") (pintype "passive"))
      (node (ref "U$6") (pin "P$21") (pinfunction "HOP_P$21") (pintype "bidirectional"))
    )
    (net (code "67") (name "Net-(U$6-LON)") (class "Default")
      (node (ref "R33") (pin "2") (pinfunction "2_2") (pintype "passive"))
      (node (ref "U$6") (pin "P$9") (pinfunction "LON_P$9") (pintype "bidirectional"))
    )
    (net (code "68") (name "Net-(U$6-LOP)") (class "Default")
      (node (ref "R34") (pin "2") (pinfunction "2_2") (pintype "passive"))
      (node (ref "U$6") (pin "P$10") (pinfunction "LOP_P$10") (pintype "bidirectional"))
    )
    (net (code "69") (name "Net-(U$6-SSDH)") (class "Default")
      (node (ref "R35") (pin "2") (pinfunction "2_2") (pintype "passive"))
      (node (ref "U$6") (pin "P$18") (pinfunction "SSDH_P$18") (pintype "bidirectional"))
    )
    (net (code "70") (name "Net-(U$6-SSDL)") (class "Default")
      (node (ref "R32") (pin "2") (pinfunction "2_2") (pintype "passive"))
      (node (ref "U$6") (pin "P$7") (pinfunction "SSDL_P$7") (pintype "bidirectional"))
    )
    (net (code "71") (name "Net-(U$6-VB)") (class "Default")
      (node (ref "C11") (pin "1") (pinfunction "1_1") (pintype "passive"))
      (node (ref "D9") (pin "C") (pinfunction "C_C") (pintype "passive"))
      (node (ref "U$6") (pin "P$23") (pinfunction "VB_P$23") (pintype "bidirectional"))
    )
    (net (code "72") (name "Net-(U$7-G)") (class "Default")
      (node (ref "R35") (pin "1") (pinfunction "1_1") (pintype "passive"))
      (node (ref "R36") (pin "1") (pinfunction "1_1") (pintype "passive"))
      (node (ref "R37") (pin "1") (pinfunction "1_1") (pintype "passive"))
      (node (ref "U$7") (pin "1") (pinfunction "G_1") (pintype "passive"))
    )
    (net (code "73") (name "Net-(U$8-G)") (class "Default")
      (node (ref "R32") (pin "1") (pinfunction "1_1") (pintype "passive"))
      (node (ref "R33") (pin "1") (pinfunction "1_1") (pintype "passive"))
      (node (ref "R34") (pin "1") (pinfunction "1_1") (pintype "passive"))
      (node (ref "U$8") (pin "1") (pinfunction "G_1") (pintype "passive"))
    )
    (net (code "74") (name "Net-(U$9-DSH)") (class "Default")
      (node (ref "R39") (pin "1") (pinfunction "1_1") (pintype "passive"))
      (node (ref "U$9") (pin "P$24") (pinfunction "DSH_P$24") (pintype "bidirectional"))
    )
    (net (code "75") (name "Net-(U$9-DSL)") (class "Default")
      (node (ref "R40") (pin "1") (pinfunction "1_1") (pintype "passive"))
      (node (ref "U$9") (pin "P$12") (pinfunction "DSL_P$12") (pintype "bidirectional"))
    )
    (net (code "76") (name "Net-(U$9-HON)") (class "Default")
      (node (ref "R45") (pin "2") (pinfunction "2_2") (pintype "passive"))
      (node (ref "U$9") (pin "P$20") (pinfunction "HON_P$20") (pintype "bidirectional"))
    )
    (net (code "77") (name "Net-(U$9-HOP)") (class "Default")
      (node (ref "R46") (pin "2") (pinfunction "2_2") (pintype "passive"))
      (node (ref "U$9") (pin "P$21") (pinfunction "HOP_P$21") (pintype "bidirectional"))
    )
    (net (code "78") (name "Net-(U$9-LON)") (class "Default")
      (node (ref "R42") (pin "2") (pinfunction "2_2") (pintype "passive"))
      (node (ref "U$9") (pin "P$9") (pinfunction "LON_P$9") (pintype "bidirectional"))
    )
    (net (code "79") (name "Net-(U$9-LOP)") (class "Default")
      (node (ref "R43") (pin "2") (pinfunction "2_2") (pintype "passive"))
      (node (ref "U$9") (pin "P$10") (pinfunction "LOP_P$10") (pintype "bidirectional"))
    )
    (net (code "80") (name "Net-(U$9-SSDH)") (class "Default")
      (node (ref "R44") (pin "2") (pinfunction "2_2") (pintype "passive"))
      (node (ref "U$9") (pin "P$18") (pinfunction "SSDH_P$18") (pintype "bidirectional"))
    )
    (net (code "81") (name "Net-(U$9-SSDL)") (class "Default")
      (node (ref "R41") (pin "2") (pinfunction "2_2") (pintype "passive"))
      (node (ref "U$9") (pin "P$7") (pinfunction "SSDL_P$7") (pintype "bidirectional"))
    )
    (net (code "82") (name "Net-(U$9-VB)") (class "Default")
      (node (ref "C13") (pin "1") (pinfunction "1_1") (pintype "passive"))
      (node (ref "D12") (pin "C") (pinfunction "C_C") (pintype "passive"))
      (node (ref "U$9") (pin "P$23") (pinfunction "VB_P$23") (pintype "bidirectional"))
    )
    (net (code "83") (name "Net-(U$10-G)") (class "Default")
      (node (ref "R44") (pin "1") (pinfunction "1_1") (pintype "passive"))
      (node (ref "R45") (pin "1") (pinfunction "1_1") (pintype "passive"))
      (node (ref "R46") (pin "1") (pinfunction "1_1") (pintype "passive"))
      (node (ref "U$10") (pin "1") (pinfunction "G_1") (pintype "passive"))
    )
    (net (code "84") (name "Net-(U$11-G)") (class "Default")
      (node (ref "R41") (pin "1") (pinfunction "1_1") (pintype "passive"))
      (node (ref "R42") (pin "1") (pinfunction "1_1") (pintype "passive"))
      (node (ref "R43") (pin "1") (pinfunction "1_1") (pintype "passive"))
      (node (ref "U$11") (pin "1") (pinfunction "G_1") (pintype "passive"))
    )
    (net (code "85") (name "PE") (class "Default")
      (node (ref "C10") (pin "2") (pinfunction "2_2") (pintype "passive"))
      (node (ref "C12") (pin "2") (pinfunction "2_2") (pintype "passive"))
      (node (ref "C14") (pin "2") (pinfunction "2_2") (pintype "passive"))
      (node (ref "C2") (pin "2") (pinfunction "2_2") (pintype "passive"))
      (node (ref "C3") (pin "2") (pinfunction "2_2") (pintype "passive"))
      (node (ref "C4") (pin "2") (pinfunction "2_2") (pintype "passive"))
      (node (ref "C6") (pin "2") (pinfunction "2_2") (pintype "passive"))
      (node (ref "C9") (pin "2") (pinfunction "2_2") (pintype "passive"))
      (node (ref "D1") (pin "A") (pinfunction "A_A") (pintype "passive"))
      (node (ref "D2") (pin "A") (pinfunction "A_A") (pintype "passive"))
      (node (ref "D6") (pin "A") (pinfunction "A_A") (pintype "passive"))
      (node (ref "D8") (pin "A") (pinfunction "A_A") (pintype "passive"))
      (node (ref "EARTH1") (pin "1") (pinfunction "P_1") (pintype "passive"))
      (node (ref "EARTH2") (pin "1") (pinfunction "P_1") (pintype "passive"))
      (node (ref "R11") (pin "1") (pinfunction "1_1") (pintype "passive"))
      (node (ref "R13") (pin "1") (pinfunction "1_1") (pintype "passive"))
      (node (ref "R14") (pin "1") (pinfunction "1_1") (pintype "passive"))
      (node (ref "R24") (pin "1") (pinfunction "1_1") (pintype "passive"))
      (node (ref "R28") (pin "1") (pinfunction "1_1") (pintype "passive"))
      (node (ref "R47") (pin "1") (pinfunction "1_1") (pintype "passive"))
      (node (ref "U$11") (pin "3") (pinfunction "S_3") (pintype "passive"))
      (node (ref "U$12") (pin "2") (pinfunction "2_2") (pintype "passive"))
      (node (ref "U$12") (pin "3") (pinfunction "2_3") (pintype "passive"))
      (node (ref "U$12") (pin "4") (pinfunction "2_4") (pintype "passive"))
      (node (ref "U$12") (pin "5") (pinfunction "2_5") (pintype "passive"))
      (node (ref "U$13") (pin "2") (pinfunction "2_2") (pintype "passive"))
      (node (ref "U$13") (pin "3") (pinfunction "2_3") (pintype "passive"))
      (node (ref "U$13") (pin "4") (pinfunction "2_4") (pintype "passive"))
      (node (ref "U$13") (pin "5") (pinfunction "2_5") (pintype "passive"))
      (node (ref "U$6") (pin "P$6") (pinfunction "VSS_P$6") (pintype "bidirectional"))
      (node (ref "U$6") (pin "P$8") (pinfunction "COM_P$8") (pintype "bidirectional"))
      (node (ref "U$8") (pin "3") (pinfunction "S_3") (pintype "passive"))
      (node (ref "U$9") (pin "P$6") (pinfunction "VSS_P$6") (pintype "bidirectional"))
      (node (ref "U$9") (pin "P$8") (pinfunction "COM_P$8") (pintype "bidirectional"))
    )
  )
)
